# Power_MCU.net
KiCad netlist of a schematic drawn in Altium Designer
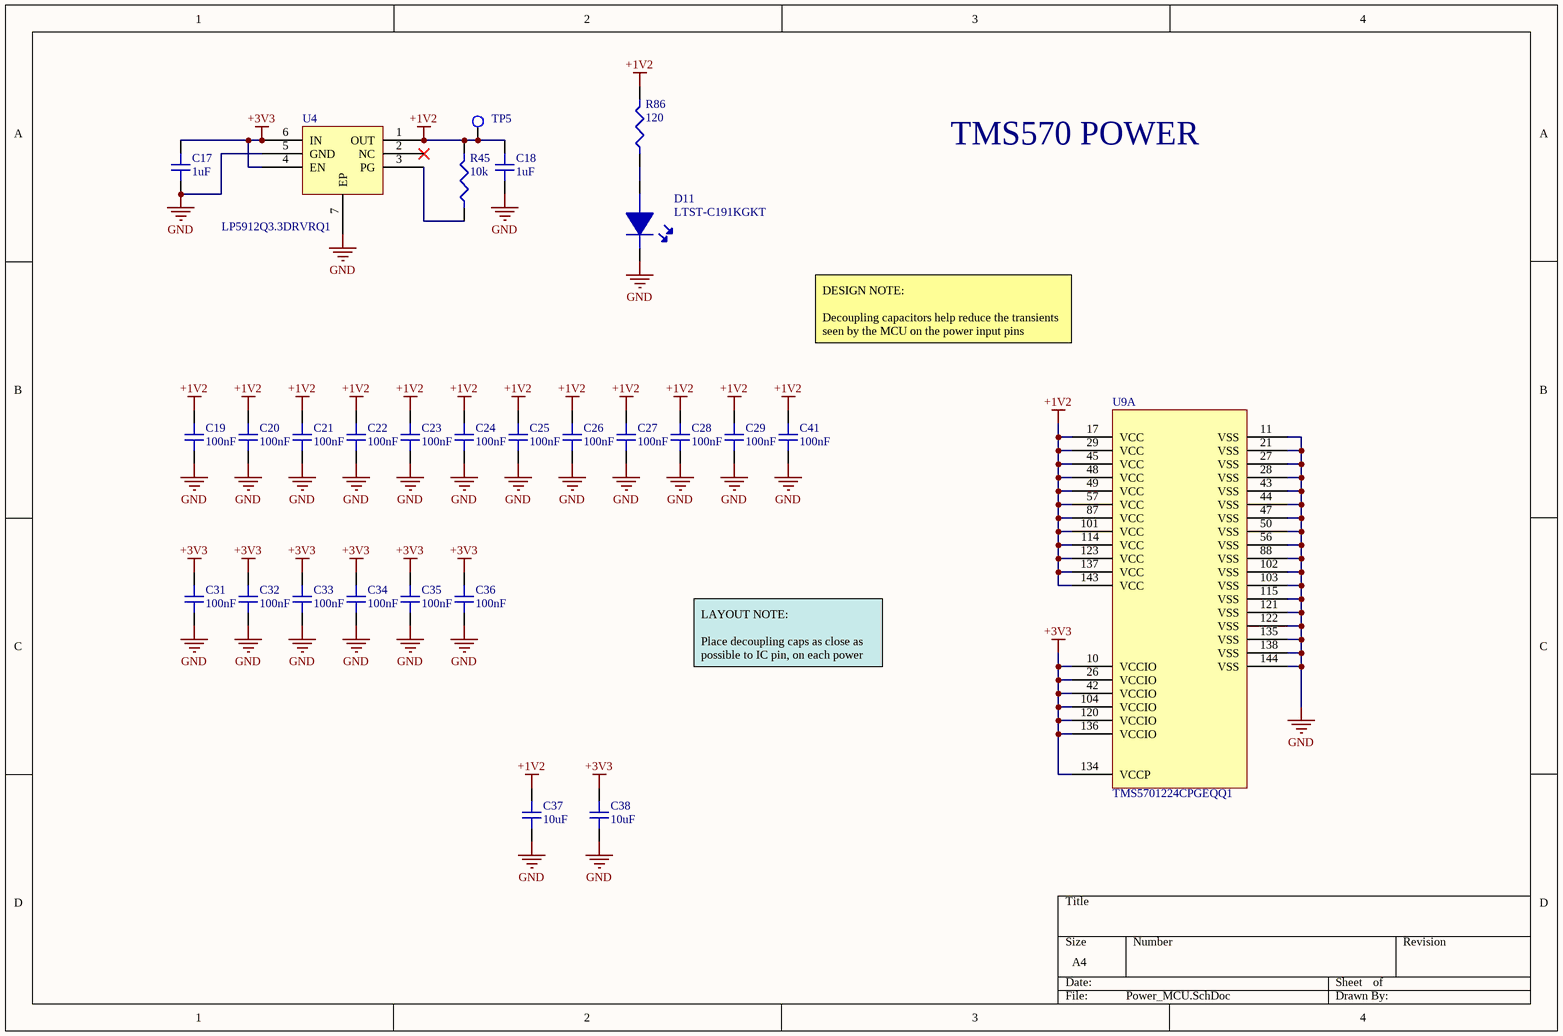
[diagram p0: Power_MCU.SchDoc]

(export (version "E")
  (design (tool "Eeschema 10.0.6"))
  (components
    (comp (ref "C17")
      (value "1uF")
      (footprint "C0805")
      (description "CAP CER 1UF 10V X7R 0805")
      (fields
        (field (name "MANUFACTURER") "Kyocera AVX")
        (field (name "MANUFACTURER PART NUMBER") "0805ZC105KAT2A")
      )
      (libsource (lib "PHANTOM_LIBRARY") (part "0805ZC105KAT2A"))
    )
    (comp (ref "C18")
      (value "1uF")
      (footprint "C0805")
      (description "CAP CER 1UF 10V X7R 0805")
      (fields
        (field (name "MANUFACTURER") "Kyocera AVX")
        (field (name "MANUFACTURER PART NUMBER") "0805ZC105KAT2A")
      )
      (libsource (lib "PHANTOM_LIBRARY") (part "0805ZC105KAT2A"))
    )
    (comp (ref "C19")
      (value "100nF")
      (footprint "PHANTOM_FOOTPRINTS:C0805")
      (description "CAP MLCC 100nF 10Volts U2J 5%")
      (fields
        (field (name "MANUFACTURER") "Murata")
        (field (name "MANUFACTURER PART NUMBER") "GRM21B7U1A104JA01L")
      )
      (libsource (lib "PHANTOM_LIBRARY") (part "GRM21B7U1A104JA01L"))
    )
    (comp (ref "C20")
      (value "100nF")
      (footprint "PHANTOM_FOOTPRINTS:C0805")
      (description "CAP MLCC 100nF 10Volts U2J 5%")
      (fields
        (field (name "MANUFACTURER") "Murata")
        (field (name "MANUFACTURER PART NUMBER") "GRM21B7U1A104JA01L")
      )
      (libsource (lib "PHANTOM_LIBRARY") (part "GRM21B7U1A104JA01L"))
    )
    (comp (ref "C21")
      (value "100nF")
      (footprint "PHANTOM_FOOTPRINTS:C0805")
      (description "CAP MLCC 100nF 10Volts U2J 5%")
      (fields
        (field (name "MANUFACTURER") "Murata")
        (field (name "MANUFACTURER PART NUMBER") "GRM21B7U1A104JA01L")
      )
      (libsource (lib "PHANTOM_LIBRARY") (part "GRM21B7U1A104JA01L"))
    )
    (comp (ref "C22")
      (value "100nF")
      (footprint "PHANTOM_FOOTPRINTS:C0805")
      (description "CAP MLCC 100nF 10Volts U2J 5%")
      (fields
        (field (name "MANUFACTURER") "Murata")
        (field (name "MANUFACTURER PART NUMBER") "GRM21B7U1A104JA01L")
      )
      (libsource (lib "PHANTOM_LIBRARY") (part "GRM21B7U1A104JA01L"))
    )
    (comp (ref "C23")
      (value "100nF")
      (footprint "PHANTOM_FOOTPRINTS:C0805")
      (description "CAP MLCC 100nF 10Volts U2J 5%")
      (fields
        (field (name "MANUFACTURER") "Murata")
        (field (name "MANUFACTURER PART NUMBER") "GRM21B7U1A104JA01L")
      )
      (libsource (lib "PHANTOM_LIBRARY") (part "GRM21B7U1A104JA01L"))
    )
    (comp (ref "C24")
      (value "100nF")
      (footprint "PHANTOM_FOOTPRINTS:C0805")
      (description "CAP MLCC 100nF 10Volts U2J 5%")
      (fields
        (field (name "MANUFACTURER") "Murata")
        (field (name "MANUFACTURER PART NUMBER") "GRM21B7U1A104JA01L")
      )
      (libsource (lib "PHANTOM_LIBRARY") (part "GRM21B7U1A104JA01L"))
    )
    (comp (ref "C25")
      (value "100nF")
      (footprint "PHANTOM_FOOTPRINTS:C0805")
      (description "CAP MLCC 100nF 10Volts U2J 5%")
      (fields
        (field (name "MANUFACTURER") "Murata")
        (field (name "MANUFACTURER PART NUMBER") "GRM21B7U1A104JA01L")
      )
      (libsource (lib "PHANTOM_LIBRARY") (part "GRM21B7U1A104JA01L"))
    )
    (comp (ref "C26")
      (value "100nF")
      (footprint "PHANTOM_FOOTPRINTS:C0805")
      (description "CAP MLCC 100nF 10Volts U2J 5%")
      (fields
        (field (name "MANUFACTURER") "Murata")
        (field (name "MANUFACTURER PART NUMBER") "GRM21B7U1A104JA01L")
      )
      (libsource (lib "PHANTOM_LIBRARY") (part "GRM21B7U1A104JA01L"))
    )
    (comp (ref "C27")
      (value "100nF")
      (footprint "PHANTOM_FOOTPRINTS:C0805")
      (description "CAP MLCC 100nF 10Volts U2J 5%")
      (fields
        (field (name "MANUFACTURER") "Murata")
        (field (name "MANUFACTURER PART NUMBER") "GRM21B7U1A104JA01L")
      )
      (libsource (lib "PHANTOM_LIBRARY") (part "GRM21B7U1A104JA01L"))
    )
    (comp (ref "C28")
      (value "100nF")
      (footprint "PHANTOM_FOOTPRINTS:C0805")
      (description "CAP MLCC 100nF 10Volts U2J 5%")
      (fields
        (field (name "MANUFACTURER") "Murata")
        (field (name "MANUFACTURER PART NUMBER") "GRM21B7U1A104JA01L")
      )
      (libsource (lib "PHANTOM_LIBRARY") (part "GRM21B7U1A104JA01L"))
    )
    (comp (ref "C29")
      (value "100nF")
      (footprint "PHANTOM_FOOTPRINTS:C0805")
      (description "CAP MLCC 100nF 10Volts U2J 5%")
      (fields
        (field (name "MANUFACTURER") "Murata")
        (field (name "MANUFACTURER PART NUMBER") "GRM21B7U1A104JA01L")
      )
      (libsource (lib "PHANTOM_LIBRARY") (part "GRM21B7U1A104JA01L"))
    )
    (comp (ref "C31")
      (value "100nF")
      (footprint "PHANTOM_FOOTPRINTS:C0805")
      (description "CAP MLCC 100nF 10Volts U2J 5%")
      (fields
        (field (name "MANUFACTURER") "Murata")
        (field (name "MANUFACTURER PART NUMBER") "GRM21B7U1A104JA01L")
      )
      (libsource (lib "PHANTOM_LIBRARY") (part "GRM21B7U1A104JA01L"))
    )
    (comp (ref "C32")
      (value "100nF")
      (footprint "PHANTOM_FOOTPRINTS:C0805")
      (description "CAP MLCC 100nF 10Volts U2J 5%")
      (fields
        (field (name "MANUFACTURER") "Murata")
        (field (name "MANUFACTURER PART NUMBER") "GRM21B7U1A104JA01L")
      )
      (libsource (lib "PHANTOM_LIBRARY") (part "GRM21B7U1A104JA01L"))
    )
    (comp (ref "C33")
      (value "100nF")
      (footprint "PHANTOM_FOOTPRINTS:C0805")
      (description "CAP MLCC 100nF 10Volts U2J 5%")
      (fields
        (field (name "MANUFACTURER") "Murata")
        (field (name "MANUFACTURER PART NUMBER") "GRM21B7U1A104JA01L")
      )
      (libsource (lib "PHANTOM_LIBRARY") (part "GRM21B7U1A104JA01L"))
    )
    (comp (ref "C34")
      (value "100nF")
      (footprint "PHANTOM_FOOTPRINTS:C0805")
      (description "CAP MLCC 100nF 10Volts U2J 5%")
      (fields
        (field (name "MANUFACTURER") "Murata")
        (field (name "MANUFACTURER PART NUMBER") "GRM21B7U1A104JA01L")
      )
      (libsource (lib "PHANTOM_LIBRARY") (part "GRM21B7U1A104JA01L"))
    )
    (comp (ref "C35")
      (value "100nF")
      (footprint "PHANTOM_FOOTPRINTS:C0805")
      (description "CAP MLCC 100nF 10Volts U2J 5%")
      (fields
        (field (name "MANUFACTURER") "Murata")
        (field (name "MANUFACTURER PART NUMBER") "GRM21B7U1A104JA01L")
      )
      (libsource (lib "PHANTOM_LIBRARY") (part "GRM21B7U1A104JA01L"))
    )
    (comp (ref "C36")
      (value "100nF")
      (footprint "PHANTOM_FOOTPRINTS:C0805")
      (description "CAP MLCC 100nF 10Volts U2J 5%")
      (fields
        (field (name "MANUFACTURER") "Murata")
        (field (name "MANUFACTURER PART NUMBER") "GRM21B7U1A104JA01L")
      )
      (libsource (lib "PHANTOM_LIBRARY") (part "GRM21B7U1A104JA01L"))
    )
    (comp (ref "C37")
      (value "10uF")
      (footprint "TANT_10u")
      (fields
        (field (name "MANUFACTURER") "Kyocera AVX")
        (field (name "MANUFACTURER PART NUMBER") "F381A106MMA")
        (field (name "TOLERANCE") "20%")
      )
      (libsource (lib "PHANTOM_LIBRARY") (part "F381A106MMA"))
    )
    (comp (ref "C38")
      (value "10uF")
      (footprint "TANT_10u")
      (fields
        (field (name "MANUFACTURER") "Kyocera AVX")
        (field (name "MANUFACTURER PART NUMBER") "F381A106MMA")
        (field (name "TOLERANCE") "20%")
      )
      (libsource (lib "PHANTOM_LIBRARY") (part "F381A106MMA"))
    )
    (comp (ref "C41")
      (value "100nF")
      (footprint "PHANTOM_FOOTPRINTS:C0805")
      (description "CAP MLCC 100nF 10Volts U2J 5%")
      (fields
        (field (name "MANUFACTURER") "Murata")
        (field (name "MANUFACTURER PART NUMBER") "GRM21B7U1A104JA01L")
      )
      (libsource (lib "PHANTOM_LIBRARY") (part "GRM21B7U1A104JA01L"))
    )
    (comp (ref "D11")
      (value "LTST-C191KGKT")
      (footprint "LED_0603")
      (description "LED GREEN CLEAR 0603 SMD")
      (fields (field (name "MANUFACTURER") "Vishay Lite-On"))
      (libsource (lib "PHANTOM_LIBRARY") (part "LTST-C191KGKT"))
    )
    (comp (ref "R45")
      (value "10k")
      (footprint "R0805")
      (description "RES SMD 10K OHM 1% 1/8W 0805")
      (fields
        (field (name "MANUFACTURER") "Yageo Phycomp")
        (field (name "MANUFACTURER PART NUMBER") "RC0805FR-071KL")
      )
      (libsource (lib "PHANTOM_LIBRARY") (part "RC0805FR-071KL"))
    )
    (comp (ref "R86")
      (value "120")
      (footprint "R0805")
      (description "RES SMD 120 OHM 1% 1/8W 0805")
      (fields
        (field (name "MANUFACTURER") "Yageo")
        (field (name "MANUFACTURER PART NUMBER") "RC0805FR-07120RL")
      )
      (libsource (lib "PHANTOM_LIBRARY") (part "RC0805FR-07120RL"))
    )
    (comp (ref "TP5")
      (value "5015")
      (footprint "TP_HOOK")
      (description "TEST POINT, PCB, SMT")
      (fields (field (name "MANUFACTURER") "Keystone Electronics"))
      (libsource (lib "PHANTOM_LIBRARY") (part "5015"))
    )
    (comp (ref "U4")
      (value "LP5912Q3.3DRVRQ1")
      (footprint "WSON")
      (description "LDO_1V2 REG 3.3V INPUT 1V2 OUTPUT 0.5A")
      (fields (field (name "MANUFACTURER") "Texas Instruments"))
      (libsource (lib "PHANTOM_LIBRARY") (part "LP5912Q3.3DRVRQ1"))
    )
    (comp (ref "U9")
      (value "TMS5701224CPGEQQ1")
      (footprint "LQFP-144")
      (description "ARM CORTEX R4 LOCK STEP HERCULES MCU")
      (fields (field (name "MANUFACTURER") "Texas Instruments"))
      (libsource (lib "PHANTOM_LIBRARY") (part "TMS5701224CPGEQQ1"))
    )
  )
  (nets
    (net (code "1") (name "+1V2") (class "Default")
      (node (ref "C18") (pin "2") (pinfunction "2_2") (pintype "passive"))
      (node (ref "C19") (pin "2") (pinfunction "2_2") (pintype "passive"))
      (node (ref "C20") (pin "2") (pinfunction "2_2") (pintype "passive"))
      (node (ref "C21") (pin "2") (pinfunction "2_2") (pintype "passive"))
      (node (ref "C22") (pin "2") (pinfunction "2_2") (pintype "passive"))
      (node (ref "C23") (pin "2") (pinfunction "2_2") (pintype "passive"))
      (node (ref "C24") (pin "2") (pinfunction "2_2") (pintype "passive"))
      (node (ref "C25") (pin "2") (pinfunction "2_2") (pintype "passive"))
      (node (ref "C26") (pin "2") (pinfunction "2_2") (pintype "passive"))
      (node (ref "C27") (pin "2") (pinfunction "2_2") (pintype "passive"))
      (node (ref "C28") (pin "2") (pinfunction "2_2") (pintype "passive"))
      (node (ref "C29") (pin "2") (pinfunction "2_2") (pintype "passive"))
      (node (ref "C37") (pin "2") (pinfunction "2_2") (pintype "passive"))
      (node (ref "C41") (pin "2") (pinfunction "2_2") (pintype "passive"))
      (node (ref "R45") (pin "2") (pinfunction "2_2") (pintype "passive"))
      (node (ref "R86") (pin "2") (pinfunction "2_2") (pintype "passive"))
      (node (ref "TP5") (pin "1") (pinfunction "1_1") (pintype "passive"))
      (node (ref "U4") (pin "1") (pinfunction "OUT_1") (pintype "passive"))
      (node (ref "U9") (pin "101") (pinfunction "VCC_101") (pintype "passive"))
      (node (ref "U9") (pin "114") (pinfunction "VCC_114") (pintype "passive"))
      (node (ref "U9") (pin "123") (pinfunction "VCC_123") (pintype "passive"))
      (node (ref "U9") (pin "137") (pinfunction "VCC_137") (pintype "passive"))
      (node (ref "U9") (pin "143") (pinfunction "VCC_143") (pintype "passive"))
      (node (ref "U9") (pin "17") (pinfunction "VCC_17") (pintype "passive"))
      (node (ref "U9") (pin "29") (pinfunction "VCC_29") (pintype "passive"))
      (node (ref "U9") (pin "45") (pinfunction "VCC_45") (pintype "passive"))
      (node (ref "U9") (pin "48") (pinfunction "VCC_48") (pintype "passive"))
      (node (ref "U9") (pin "49") (pinfunction "VCC_49") (pintype "passive"))
      (node (ref "U9") (pin "57") (pinfunction "VCC_57") (pintype "passive"))
      (node (ref "U9") (pin "87") (pinfunction "VCC_87") (pintype "passive"))
    )
    (net (code "2") (name "+3V3") (class "Default")
      (node (ref "C17") (pin "2") (pinfunction "2_2") (pintype "passive"))
      (node (ref "C31") (pin "2") (pinfunction "2_2") (pintype "passive"))
      (node (ref "C32") (pin "2") (pinfunction "2_2") (pintype "passive"))
      (node (ref "C33") (pin "2") (pinfunction "2_2") (pintype "passive"))
      (node (ref "C34") (pin "2") (pinfunction "2_2") (pintype "passive"))
      (node (ref "C35") (pin "2") (pinfunction "2_2") (pintype "passive"))
      (node (ref "C36") (pin "2") (pinfunction "2_2") (pintype "passive"))
      (node (ref "C38") (pin "2") (pinfunction "2_2") (pintype "passive"))
      (node (ref "U4") (pin "4") (pinfunction "EN_4") (pintype "passive"))
      (node (ref "U4") (pin "6") (pinfunction "IN_6") (pintype "passive"))
      (node (ref "U9") (pin "10") (pinfunction "VCCIO_10") (pintype "passive"))
      (node (ref "U9") (pin "104") (pinfunction "VCCIO_104") (pintype "passive"))
      (node (ref "U9") (pin "120") (pinfunction "VCCIO_120") (pintype "passive"))
      (node (ref "U9") (pin "134") (pinfunction "VCCP_134") (pintype "passive"))
      (node (ref "U9") (pin "136") (pinfunction "VCCIO_136") (pintype "passive"))
      (node (ref "U9") (pin "26") (pinfunction "VCCIO_26") (pintype "passive"))
      (node (ref "U9") (pin "42") (pinfunction "VCCIO_42") (pintype "passive"))
    )
    (net (code "3") (name "GND") (class "Default")
      (node (ref "C17") (pin "1") (pinfunction "1_1") (pintype "passive"))
      (node (ref "C18") (pin "1") (pinfunction "1_1") (pintype "passive"))
      (node (ref "C19") (pin "1") (pinfunction "1_1") (pintype "passive"))
      (node (ref "C20") (pin "1") (pinfunction "1_1") (pintype "passive"))
      (node (ref "C21") (pin "1") (pinfunction "1_1") (pintype "passive"))
      (node (ref "C22") (pin "1") (pinfunction "1_1") (pintype "passive"))
      (node (ref "C23") (pin "1") (pinfunction "1_1") (pintype "passive"))
      (node (ref "C24") (pin "1") (pinfunction "1_1") (pintype "passive"))
      (node (ref "C25") (pin "1") (pinfunction "1_1") (pintype "passive"))
      (node (ref "C26") (pin "1") (pinfunction "1_1") (pintype "passive"))
      (node (ref "C27") (pin "1") (pinfunction "1_1") (pintype "passive"))
      (node (ref "C28") (pin "1") (pinfunction "1_1") (pintype "passive"))
      (node (ref "C29") (pin "1") (pinfunction "1_1") (pintype "passive"))
      (node (ref "C31") (pin "1") (pinfunction "1_1") (pintype "passive"))
      (node (ref "C32") (pin "1") (pinfunction "1_1") (pintype "passive"))
      (node (ref "C33") (pin "1") (pinfunction "1_1") (pintype "passive"))
      (node (ref "C34") (pin "1") (pinfunction "1_1") (pintype "passive"))
      (node (ref "C35") (pin "1") (pinfunction "1_1") (pintype "passive"))
      (node (ref "C36") (pin "1") (pinfunction "1_1") (pintype "passive"))
      (node (ref "C37") (pin "1") (pinfunction "1_1") (pintype "passive"))
      (node (ref "C38") (pin "1") (pinfunction "1_1") (pintype "passive"))
      (node (ref "C41") (pin "1") (pinfunction "1_1") (pintype "passive"))
      (node (ref "D11") (pin "2") (pinfunction "2_2") (pintype "passive"))
      (node (ref "U4") (pin "5") (pinfunction "GND_5") (pintype "passive"))
      (node (ref "U4") (pin "7") (pinfunction "EP_7") (pintype "passive"))
      (node (ref "U9") (pin "102") (pinfunction "VSS_102") (pintype "passive"))
      (node (ref "U9") (pin "103") (pinfunction "VSS_103") (pintype "passive"))
      (node (ref "U9") (pin "11") (pinfunction "VSS_11") (pintype "passive"))
      (node (ref "U9") (pin "115") (pinfunction "VSS_115") (pintype "passive"))
      (node (ref "U9") (pin "121") (pinfunction "VSS_121") (pintype "passive"))
      (node (ref "U9") (pin "122") (pinfunction "VSS_122") (pintype "passive"))
      (node (ref "U9") (pin "135") (pinfunction "VSS_135") (pintype "passive"))
      (node (ref "U9") (pin "138") (pinfunction "VSS_138") (pintype "passive"))
      (node (ref "U9") (pin "144") (pinfunction "VSS_144") (pintype "passive"))
      (node (ref "U9") (pin "21") (pinfunction "VSS_21") (pintype "passive"))
      (node (ref "U9") (pin "27") (pinfunction "VSS_27") (pintype "passive"))
      (node (ref "U9") (pin "28") (pinfunction "VSS_28") (pintype "passive"))
      (node (ref "U9") (pin "43") (pinfunction "VSS_43") (pintype "passive"))
      (node (ref "U9") (pin "44") (pinfunction "VSS_44") (pintype "passive"))
      (node (ref "U9") (pin "47") (pinfunction "VSS_47") (pintype "passive"))
      (node (ref "U9") (pin "50") (pinfunction "VSS_50") (pintype "passive"))
      (node (ref "U9") (pin "56") (pinfunction "VSS_56") (pintype "passive"))
      (node (ref "U9") (pin "88") (pinfunction "VSS_88") (pintype "passive"))
    )
    (net (code "4") (name "Net-(D11-Pad1)") (class "Default")
      (node (ref "D11") (pin "1") (pinfunction "1_1") (pintype "passive"))
      (node (ref "R86") (pin "1") (pinfunction "1_1") (pintype "passive"))
    )
    (net (code "5") (name "Net-(U4-PG)") (class "Default")
      (node (ref "R45") (pin "1") (pinfunction "1_1") (pintype "passive"))
      (node (ref "U4") (pin "3") (pinfunction "PG_3") (pintype "passive"))
    )
    (net (code "6") (name "unconnected-(U4-NC-Pad2)") (class "Default")
      (node (ref "U4") (pin "2") (pinfunction "NC_2") (pintype "passive+no_connect"))
    )
  )
)
